# Sheet1.net
KiCad netlist of a schematic drawn in Altium Designer
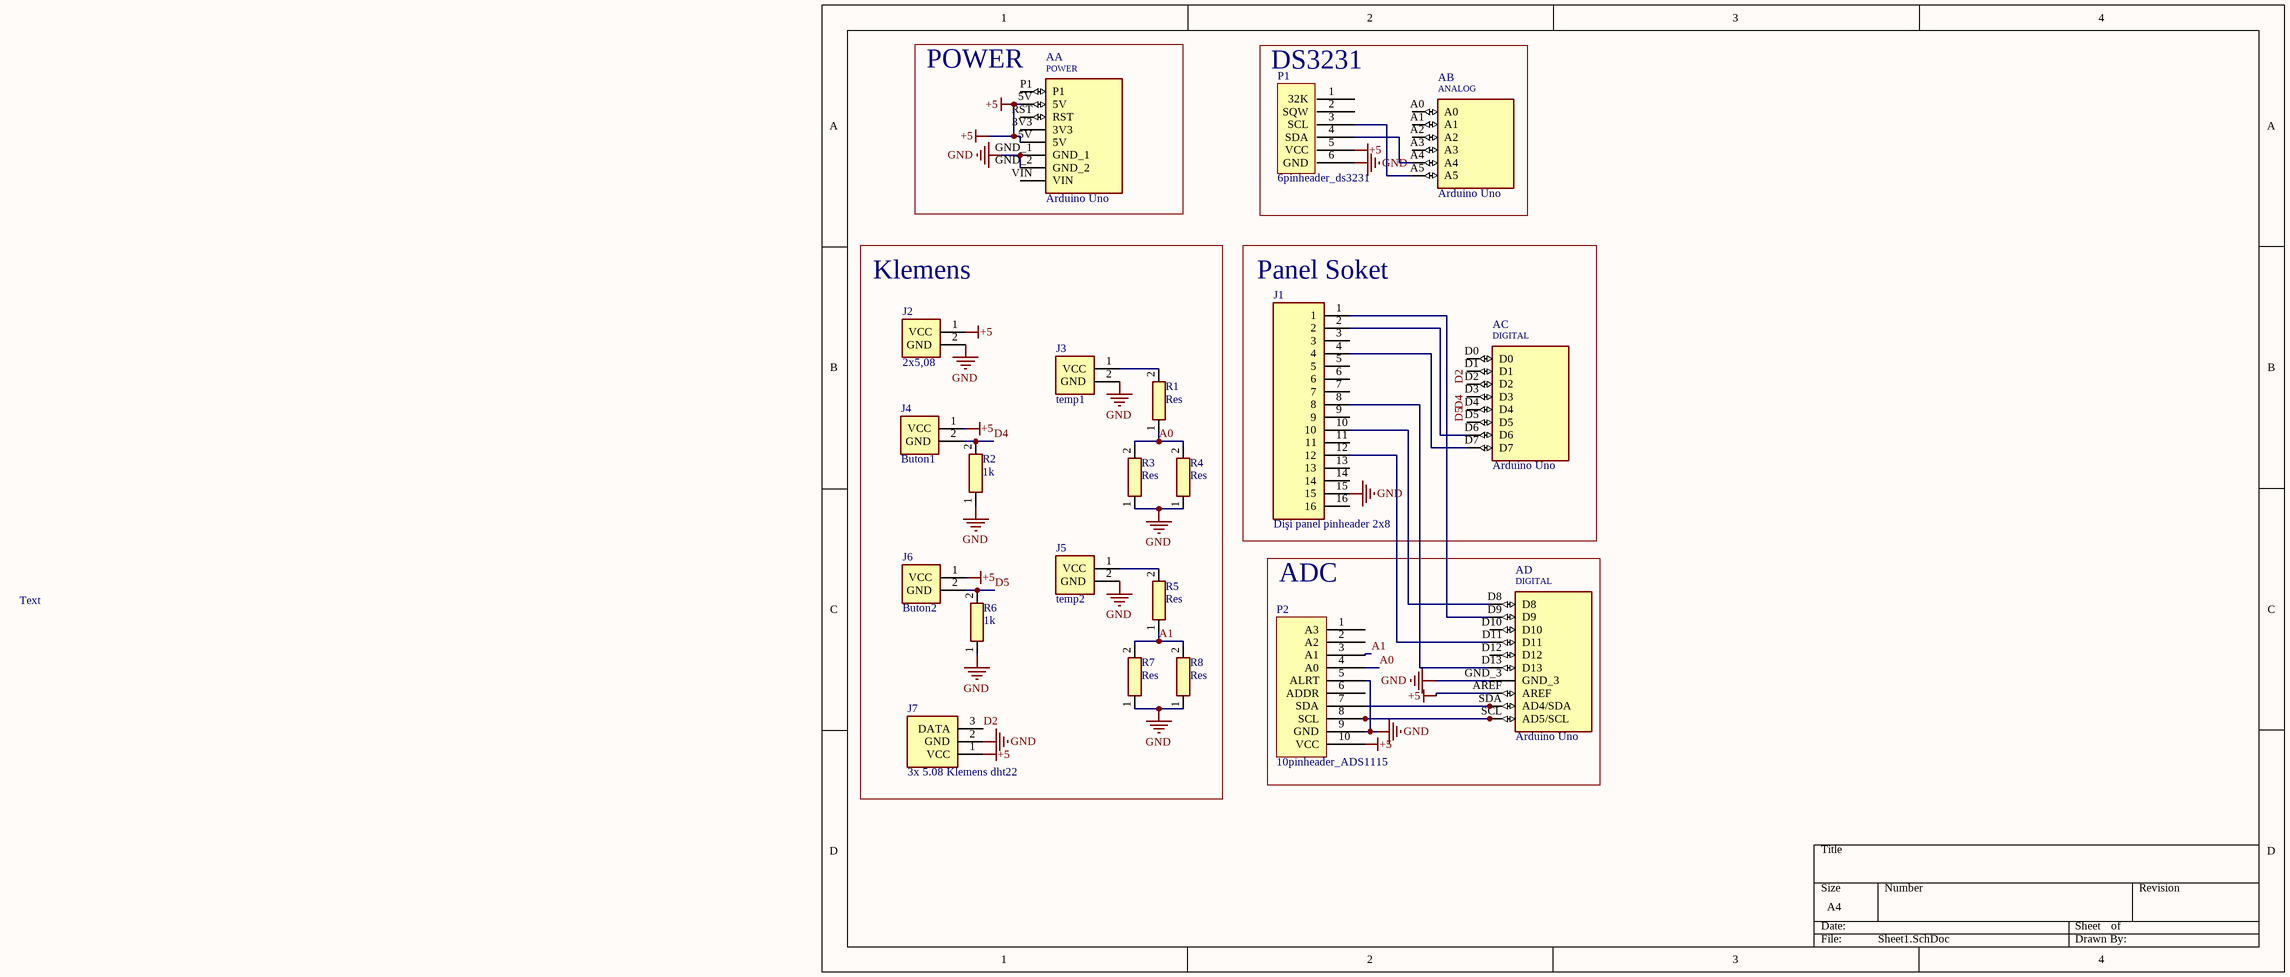
[diagram p0: Sheet1.SchDoc]

(export (version "E")
  (design (tool "Eeschema 10.0.6"))
  (components
    (comp (ref "A")
      (value "Arduino Uno")
      (footprint "ARDUINO_A000066")
      (description "ATmega328P Arduino Uno R3 AVRÂ® ATmega AVR MCU 8-Bit Embedded Evaluation Board")
      (fields (field (name "MF") "Arduino") (field (name "MP") "A000066"))
      (libsource (lib "Schlib2") (part "Arduino Uno"))
    )
    (comp (ref "J1")
      (value "Dişi panel pinheader 2x8")
      (footprint "Dişi panel pinheader 2x8")
      (description "IDC LOW PRO HDR 50P VERT HT BLACK")
      (fields (field (name "MP") "1761681-6"))
      (libsource (lib "Schlib2") (part "Dişi panel pinheader 2x8"))
    )
    (comp (ref "J2")
      (value "2x5,08")
      (footprint "2x5,08")
      (description "TERMINAL BLOCK,HEADER, 5.08 MM, 2WAY; Product Range:-; Gender:Header")
      (fields (field (name "MF") "TE Connectivity") (field (name "MP") "282814-2"))
      (libsource (lib "Schlib2") (part "2x5,08"))
    )
    (comp (ref "J3")
      (value "temp1")
      (footprint "2x5,08")
      (description "TERMINAL BLOCK,HEADER, 5.08 MM, 2WAY; Product Range:-; Gender:Header")
      (fields (field (name "MF") "TE Connectivity") (field (name "MP") "282814-2"))
      (libsource (lib "Schlib2") (part "2x5,08"))
    )
    (comp (ref "J4")
      (value "Buton1")
      (footprint "2x5,08")
      (description "TERMINAL BLOCK,HEADER, 5.08 MM, 2WAY; Product Range:-; Gender:Header")
      (fields (field (name "MF") "TE Connectivity") (field (name "MP") "282814-2"))
      (libsource (lib "Schlib2") (part "2x5,08"))
    )
    (comp (ref "J5")
      (value "temp2")
      (footprint "2x5,08")
      (description "TERMINAL BLOCK,HEADER, 5.08 MM, 2WAY; Product Range:-; Gender:Header")
      (fields (field (name "MF") "TE Connectivity") (field (name "MP") "282814-2"))
      (libsource (lib "Schlib2") (part "2x5,08"))
    )
    (comp (ref "J6")
      (value "Buton2")
      (footprint "2x5,08")
      (description "TERMINAL BLOCK,HEADER, 5.08 MM, 2WAY; Product Range:-; Gender:Header")
      (fields (field (name "MF") "TE Connectivity") (field (name "MP") "282814-2"))
      (libsource (lib "Schlib2") (part "2x5,08"))
    )
    (comp (ref "J7")
      (value "3x 5.08 Klemens dht22")
      (footprint "3x 5.08 klemens")
      (description "2~24 Poles, Screw Type, Horizontal, 5.08 Pitch, 26~14 _AWG_, Terminal Block Connector")
      (fields (field (name "MF") "CUI Devices") (field (name "MP") "TB006-508-03BE"))
      (libsource (lib "Schlib2") (part "3x 5.08 Klemens dht22"))
    )
    (comp (ref "P1")
      (value "6pinheader_ds3231")
      (footprint "6pinheader_ds3231")
      (libsource (lib "Schlib2") (part "6pinheader_ds3231"))
    )
    (comp (ref "P2")
      (value "10pinheader_ADS1115")
      (footprint "10xHeaderAD725-1")
      (libsource (lib "Schlib2") (part "10pinheader_ADS1115"))
    )
    (comp (ref "R1")
      (value "Res")
      (footprint "10k resistor")
      (description "Resistor")
      (fields
        (field (name "MANUFACTURER_PART_NUMBER") "CRCW120610K0DHEAP")
        (field (name "MOUSER PART NUMBER") "71-CRCW120610K0DHEAP")
      )
      (libsource (lib "Schlib2") (part "Res"))
    )
    (comp (ref "R2")
      (value "1k")
      (footprint "10k resistor")
      (description "Resistor")
      (fields
        (field (name "MANUFACTURER_PART_NUMBER") "CRCW120610K0DHEAP")
        (field (name "MOUSER PART NUMBER") "71-CRCW120610K0DHEAP")
      )
      (libsource (lib "Schlib2") (part "Res"))
    )
    (comp (ref "R3")
      (value "Res")
      (footprint "10k resistor")
      (description "Resistor")
      (fields
        (field (name "MANUFACTURER_PART_NUMBER") "CRCW120610K0DHEAP")
        (field (name "MOUSER PART NUMBER") "71-CRCW120610K0DHEAP")
      )
      (libsource (lib "Schlib2") (part "Res"))
    )
    (comp (ref "R4")
      (value "Res")
      (footprint "10k resistor")
      (description "Resistor")
      (fields
        (field (name "MANUFACTURER_PART_NUMBER") "CRCW120610K0DHEAP")
        (field (name "MOUSER PART NUMBER") "71-CRCW120610K0DHEAP")
      )
      (libsource (lib "Schlib2") (part "Res"))
    )
    (comp (ref "R5")
      (value "Res")
      (footprint "10k resistor")
      (description "Resistor")
      (fields
        (field (name "MANUFACTURER_PART_NUMBER") "CRCW120610K0DHEAP")
        (field (name "MOUSER PART NUMBER") "71-CRCW120610K0DHEAP")
      )
      (libsource (lib "Schlib2") (part "Res"))
    )
    (comp (ref "R6")
      (value "1k")
      (footprint "10k resistor")
      (description "Resistor")
      (fields
        (field (name "MANUFACTURER_PART_NUMBER") "CRCW120610K0DHEAP")
        (field (name "MOUSER PART NUMBER") "71-CRCW120610K0DHEAP")
      )
      (libsource (lib "Schlib2") (part "Res"))
    )
    (comp (ref "R7")
      (value "Res")
      (footprint "10k resistor")
      (description "Resistor")
      (fields
        (field (name "MANUFACTURER_PART_NUMBER") "CRCW120610K0DHEAP")
        (field (name "MOUSER PART NUMBER") "71-CRCW120610K0DHEAP")
      )
      (libsource (lib "Schlib2") (part "Res"))
    )
    (comp (ref "R8")
      (value "Res")
      (footprint "10k resistor")
      (description "Resistor")
      (fields
        (field (name "MANUFACTURER_PART_NUMBER") "CRCW120610K0DHEAP")
        (field (name "MOUSER PART NUMBER") "71-CRCW120610K0DHEAP")
      )
      (libsource (lib "Schlib2") (part "Res"))
    )
  )
  (nets
    (net (code "1") (name "+5") (class "Default")
      (node (ref "A") (pin "5V") (pinfunction "5V_5V") (pintype "bidirectional"))
      (node (ref "A") (pin "AREF") (pinfunction "AREF_AREF") (pintype "bidirectional"))
      (node (ref "J2") (pin "1") (pinfunction "VCC_1") (pintype "passive"))
      (node (ref "J4") (pin "1") (pinfunction "VCC_1") (pintype "passive"))
      (node (ref "J6") (pin "1") (pinfunction "VCC_1") (pintype "passive"))
      (node (ref "J7") (pin "1") (pinfunction "VCC_1") (pintype "passive"))
      (node (ref "P1") (pin "5") (pinfunction "VCC_5") (pintype "passive"))
      (node (ref "P2") (pin "10") (pinfunction "VCC_10") (pintype "passive"))
    )
    (net (code "2") (name "/A0") (class "Default")
      (node (ref "P2") (pin "4") (pinfunction "A0_4") (pintype "passive"))
      (node (ref "R1") (pin "1") (pinfunction "1_1") (pintype "passive"))
      (node (ref "R3") (pin "2") (pinfunction "2_2") (pintype "passive"))
      (node (ref "R4") (pin "2") (pinfunction "2_2") (pintype "passive"))
    )
    (net (code "3") (name "/A1") (class "Default")
      (node (ref "P2") (pin "3") (pinfunction "A1_3") (pintype "passive"))
      (node (ref "R5") (pin "1") (pinfunction "1_1") (pintype "passive"))
      (node (ref "R7") (pin "2") (pinfunction "2_2") (pintype "passive"))
      (node (ref "R8") (pin "2") (pinfunction "2_2") (pintype "passive"))
    )
    (net (code "4") (name "/D2") (class "Default")
      (node (ref "A") (pin "D2") (pinfunction "D2_D2") (pintype "bidirectional"))
      (node (ref "J7") (pin "3") (pinfunction "DATA_3") (pintype "passive"))
    )
    (net (code "5") (name "/D4") (class "Default")
      (node (ref "A") (pin "D4") (pinfunction "D4_D4") (pintype "bidirectional"))
      (node (ref "J4") (pin "2") (pinfunction "GND_2") (pintype "passive"))
      (node (ref "R2") (pin "2") (pinfunction "2_2") (pintype "passive"))
    )
    (net (code "6") (name "/D5") (class "Default")
      (node (ref "A") (pin "D5") (pinfunction "D5_D5") (pintype "bidirectional"))
      (node (ref "J6") (pin "2") (pinfunction "GND_2") (pintype "passive"))
      (node (ref "R6") (pin "2") (pinfunction "2_2") (pintype "passive"))
    )
    (net (code "7") (name "GND") (class "Default")
      (node (ref "A") (pin "GND_1") (pinfunction "GND_1_GND_1") (pintype "power_in"))
      (node (ref "A") (pin "GND_2") (pinfunction "GND_2_GND_2") (pintype "power_in"))
      (node (ref "A") (pin "GND_3") (pinfunction "GND_3_GND_3") (pintype "power_in"))
      (node (ref "J1") (pin "15") (pinfunction "15_15") (pintype "passive"))
      (node (ref "J2") (pin "2") (pinfunction "GND_2") (pintype "passive"))
      (node (ref "J3") (pin "2") (pinfunction "GND_2") (pintype "passive"))
      (node (ref "J5") (pin "2") (pinfunction "GND_2") (pintype "passive"))
      (node (ref "J7") (pin "2") (pinfunction "GND_2") (pintype "passive"))
      (node (ref "P1") (pin "6") (pinfunction "GND_6") (pintype "passive"))
      (node (ref "P2") (pin "5") (pinfunction "ALRT_5") (pintype "passive"))
      (node (ref "P2") (pin "9") (pinfunction "GND_9") (pintype "passive"))
      (node (ref "R2") (pin "1") (pinfunction "1_1") (pintype "passive"))
      (node (ref "R3") (pin "1") (pinfunction "1_1") (pintype "passive"))
      (node (ref "R4") (pin "1") (pinfunction "1_1") (pintype "passive"))
      (node (ref "R6") (pin "1") (pinfunction "1_1") (pintype "passive"))
      (node (ref "R7") (pin "1") (pinfunction "1_1") (pintype "passive"))
      (node (ref "R8") (pin "1") (pinfunction "1_1") (pintype "passive"))
    )
    (net (code "8") (name "Net-(A-PadD6)") (class "Default")
      (node (ref "A") (pin "D6") (pinfunction "D6_D6") (pintype "bidirectional"))
      (node (ref "J1") (pin "2") (pinfunction "2_2") (pintype "passive"))
    )
    (net (code "9") (name "Net-(A-PadD7)") (class "Default")
      (node (ref "A") (pin "D7") (pinfunction "D7_D7") (pintype "bidirectional"))
      (node (ref "J1") (pin "4") (pinfunction "4_4") (pintype "passive"))
    )
    (net (code "10") (name "Net-(A-PadD8)") (class "Default")
      (node (ref "A") (pin "D8") (pinfunction "D8_D8") (pintype "bidirectional"))
      (node (ref "J1") (pin "10") (pinfunction "10_10") (pintype "passive"))
    )
    (net (code "11") (name "Net-(A-PadD9)") (class "Default")
      (node (ref "A") (pin "D9") (pinfunction "D9_D9") (pintype "bidirectional"))
      (node (ref "J1") (pin "1") (pinfunction "1_1") (pintype "passive"))
    )
    (net (code "12") (name "Net-(A-PadD11)") (class "Default")
      (node (ref "A") (pin "D11") (pinfunction "D11_D11") (pintype "bidirectional"))
      (node (ref "J1") (pin "12") (pinfunction "12_12") (pintype "passive"))
    )
    (net (code "13") (name "Net-(A-PadD13)") (class "Default")
      (node (ref "A") (pin "D13") (pinfunction "D13_D13") (pintype "bidirectional"))
      (node (ref "J1") (pin "8") (pinfunction "8_8") (pintype "passive"))
    )
    (net (code "14") (name "Net-(AD-AD4{slash}SDA)") (class "Default")
      (node (ref "A") (pin "SDA") (pinfunction "AD4/SDA_SDA") (pintype "bidirectional"))
      (node (ref "P2") (pin "7") (pinfunction "SDA_7") (pintype "passive"))
    )
    (net (code "15") (name "Net-(AD-AD5{slash}SCL)") (class "Default")
      (node (ref "A") (pin "SCL") (pinfunction "AD5/SCL_SCL") (pintype "bidirectional"))
      (node (ref "P2") (pin "8") (pinfunction "SCL_8") (pintype "passive"))
    )
    (net (code "16") (name "Net-(J3-VCC)") (class "Default")
      (node (ref "J3") (pin "1") (pinfunction "VCC_1") (pintype "passive"))
      (node (ref "R1") (pin "2") (pinfunction "2_2") (pintype "passive"))
    )
    (net (code "17") (name "Net-(J5-VCC)") (class "Default")
      (node (ref "J5") (pin "1") (pinfunction "VCC_1") (pintype "passive"))
      (node (ref "R5") (pin "2") (pinfunction "2_2") (pintype "passive"))
    )
    (net (code "18") (name "Net-(P1-SCL)") (class "Default")
      (node (ref "A") (pin "A5") (pinfunction "A5_A5") (pintype "bidirectional"))
      (node (ref "P1") (pin "3") (pinfunction "SCL_3") (pintype "passive"))
    )
    (net (code "19") (name "Net-(P1-SDA)") (class "Default")
      (node (ref "A") (pin "A4") (pinfunction "A4_A4") (pintype "bidirectional"))
      (node (ref "P1") (pin "4") (pinfunction "SDA_4") (pintype "passive"))
    )
    (net (code "20") (name "unconnected-(A-Pad3V3)") (class "Default")
      (node (ref "A") (pin "3V3") (pinfunction "3V3_3V3") (pintype "power_in"))
    )
    (net (code "21") (name "unconnected-(A-PadA0)") (class "Default")
      (node (ref "A") (pin "A0") (pinfunction "A0_A0") (pintype "bidirectional"))
    )
    (net (code "22") (name "unconnected-(A-PadA1)") (class "Default")
      (node (ref "A") (pin "A1") (pinfunction "A1_A1") (pintype "bidirectional"))
    )
    (net (code "23") (name "unconnected-(A-PadA2)") (class "Default")
      (node (ref "A") (pin "A2") (pinfunction "A2_A2") (pintype "bidirectional"))
    )
    (net (code "24") (name "unconnected-(A-PadA3)") (class "Default")
      (node (ref "A") (pin "A3") (pinfunction "A3_A3") (pintype "bidirectional"))
    )
    (net (code "25") (name "unconnected-(A-PadD0)") (class "Default")
      (node (ref "A") (pin "D0") (pinfunction "D0_D0") (pintype "bidirectional"))
    )
    (net (code "26") (name "unconnected-(A-PadD1)") (class "Default")
      (node (ref "A") (pin "D1") (pinfunction "D1_D1") (pintype "bidirectional"))
    )
    (net (code "27") (name "unconnected-(A-PadD3)") (class "Default")
      (node (ref "A") (pin "D3") (pinfunction "D3_D3") (pintype "bidirectional"))
    )
    (net (code "28") (name "unconnected-(A-PadD10)") (class "Default")
      (node (ref "A") (pin "D10") (pinfunction "D10_D10") (pintype "bidirectional"))
    )
    (net (code "29") (name "unconnected-(A-PadD12)") (class "Default")
      (node (ref "A") (pin "D12") (pinfunction "D12_D12") (pintype "bidirectional"))
    )
    (net (code "30") (name "unconnected-(A-PadP1)") (class "Default")
      (node (ref "A") (pin "P1") (pinfunction "P1_P1") (pintype "bidirectional"))
    )
    (net (code "31") (name "unconnected-(A-PadRST)") (class "Default")
      (node (ref "A") (pin "RST") (pinfunction "RST_RST") (pintype "bidirectional"))
    )
    (net (code "32") (name "unconnected-(A-PadVIN)") (class "Default")
      (node (ref "A") (pin "VIN") (pinfunction "VIN_VIN") (pintype "power_in"))
    )
    (net (code "33") (name "unconnected-(J1-Pad3)") (class "Default")
      (node (ref "J1") (pin "3") (pinfunction "3_3") (pintype "passive"))
    )
    (net (code "34") (name "unconnected-(J1-Pad5)") (class "Default")
      (node (ref "J1") (pin "5") (pinfunction "5_5") (pintype "passive"))
    )
    (net (code "35") (name "unconnected-(J1-Pad6)") (class "Default")
      (node (ref "J1") (pin "6") (pinfunction "6_6") (pintype "passive"))
    )
    (net (code "36") (name "unconnected-(J1-Pad7)") (class "Default")
      (node (ref "J1") (pin "7") (pinfunction "7_7") (pintype "passive"))
    )
    (net (code "37") (name "unconnected-(J1-Pad9)") (class "Default")
      (node (ref "J1") (pin "9") (pinfunction "9_9") (pintype "passive"))
    )
    (net (code "38") (name "unconnected-(J1-Pad11)") (class "Default")
      (node (ref "J1") (pin "11") (pinfunction "11_11") (pintype "passive"))
    )
    (net (code "39") (name "unconnected-(J1-Pad13)") (class "Default")
      (node (ref "J1") (pin "13") (pinfunction "13_13") (pintype "passive"))
    )
    (net (code "40") (name "unconnected-(J1-Pad14)") (class "Default")
      (node (ref "J1") (pin "14") (pinfunction "14_14") (pintype "passive"))
    )
    (net (code "41") (name "unconnected-(J1-Pad16)") (class "Default")
      (node (ref "J1") (pin "16") (pinfunction "16_16") (pintype "passive"))
    )
    (net (code "42") (name "unconnected-(P1-32K-Pad1)") (class "Default")
      (node (ref "P1") (pin "1") (pinfunction "32K_1") (pintype "passive"))
    )
    (net (code "43") (name "unconnected-(P1-SQW-Pad2)") (class "Default")
      (node (ref "P1") (pin "2") (pinfunction "SQW_2") (pintype "passive"))
    )
    (net (code "44") (name "unconnected-(P2-A2-Pad2)") (class "Default")
      (node (ref "P2") (pin "2") (pinfunction "A2_2") (pintype "passive"))
    )
    (net (code "45") (name "unconnected-(P2-A3-Pad1)") (class "Default")
      (node (ref "P2") (pin "1") (pinfunction "A3_1") (pintype "passive"))
    )
    (net (code "46") (name "unconnected-(P2-ADDR-Pad6)") (class "Default")
      (node (ref "P2") (pin "6") (pinfunction "ADDR_6") (pintype "passive"))
    )
  )
)
